# QAn_IP5306_1_0.net
KiCad netlist of a schematic drawn in EAGLE
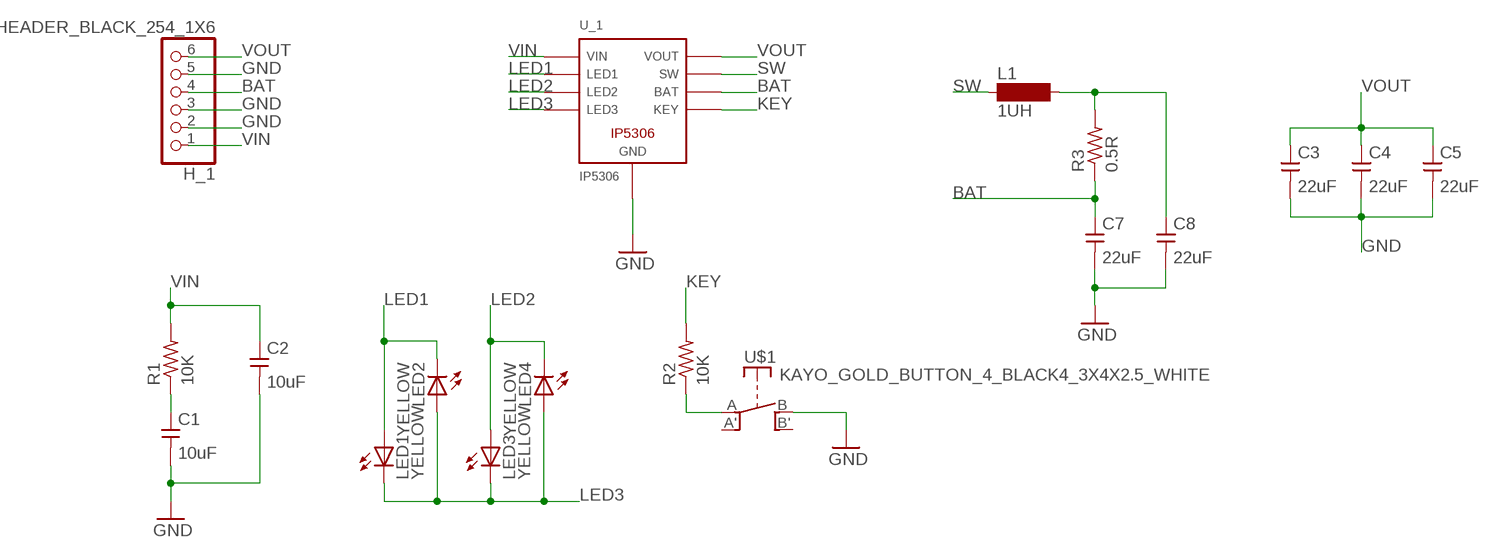
[diagram p0: schematic, sheet 1]

(export (version "E")
  (design (tool "Eeschema 10.0.6"))
  (components
    (comp (ref "C1")
      (value "10uF")
      (footprint "eagle-import:C1206")
      (libsource (lib "eagle-import") (part "KAYO_CAP_CERAMIC_120610UF"))
    )
    (comp (ref "C2")
      (value "10uF")
      (footprint "eagle-import:C1206")
      (libsource (lib "eagle-import") (part "KAYO_CAP_CERAMIC_120610UF"))
    )
    (comp (ref "C3")
      (value "22uF")
      (footprint "eagle-import:C1206")
      (libsource (lib "eagle-import") (part "KAYO_CAP_CERAMIC_120610UF"))
    )
    (comp (ref "C4")
      (value "22uF")
      (footprint "eagle-import:C1206")
      (libsource (lib "eagle-import") (part "KAYO_CAP_CERAMIC_120610UF"))
    )
    (comp (ref "C5")
      (value "22uF")
      (footprint "eagle-import:KXN_C0603")
      (libsource (lib "eagle-import") (part "KAYO_CAP_CERAMIC_KXN_060322UF"))
    )
    (comp (ref "C7")
      (value "22uF")
      (footprint "eagle-import:C1206")
      (libsource (lib "eagle-import") (part "KAYO_CAP_CERAMIC_120610UF"))
    )
    (comp (ref "C8")
      (value "22uF")
      (footprint "eagle-import:C1206")
      (libsource (lib "eagle-import") (part "KAYO_CAP_CERAMIC_120610UF"))
    )
    (comp (ref "H_1")
      (value "HEADER_BLACK_254_1X6")
      (footprint "eagle-import:HEADER_1X6_254_LOCK")
      (libsource (lib "eagle-import") (part "KXN_HEADER_1X6_M_LOCK"))
    )
    (comp (ref "L1")
      (value "1UH")
      (footprint "eagle-import:CKST_0603_0630_PACK")
      (libsource (lib "eagle-import") (part "INDUCTOR_FEEDER_KAYO_0630"))
    )
    (comp (ref "LED1")
      (value "YELLOW")
      (footprint "eagle-import:KXN_LED_0603")
      (libsource (lib "eagle-import") (part "KAYO_LED_KXN_LED_0603_YELLOW"))
    )
    (comp (ref "LED2")
      (value "YELLOW")
      (footprint "eagle-import:KXN_LED_0603")
      (libsource (lib "eagle-import") (part "KAYO_LED_KXN_LED_0603_YELLOW"))
    )
    (comp (ref "LED3")
      (value "YELLOW")
      (footprint "eagle-import:KXN_LED_0603")
      (libsource (lib "eagle-import") (part "KAYO_LED_KXN_LED_0603_YELLOW"))
    )
    (comp (ref "LED4")
      (value "YELLOW")
      (footprint "eagle-import:KXN_LED_0603")
      (libsource (lib "eagle-import") (part "KAYO_LED_KXN_LED_0603_YELLOW"))
    )
    (comp (ref "R1")
      (value "10K")
      (footprint "eagle-import:R0603_KXN")
      (libsource (lib "eagle-import") (part "R-US__R0603_KXN10K"))
    )
    (comp (ref "R2")
      (value "10K")
      (footprint "eagle-import:R0603_KXN")
      (libsource (lib "eagle-import") (part "R-US__R0603_KXN10K"))
    )
    (comp (ref "R3")
      (value "0.5R")
      (footprint "eagle-import:R0603_KXN")
      (libsource (lib "eagle-import") (part "R-US__R0603_KXN"))
    )
    (comp (ref "U$1")
      (value "KAYO_GOLD_BUTTON_4_BLACK4_3X4X2.5_WHITE")
      (footprint "eagle-import:KXN_BUTTON_3_4_2.5MM")
      (libsource (lib "eagle-import") (part "KAYO_GOLD_BUTTON_44_3X4X2.5_WHITE_BLACK"))
    )
    (comp (ref "U_1")
      (value "IP5306")
      (footprint "eagle-import:ESOP8")
      (libsource (lib "eagle-import") (part "IP5306_1"))
    )
  )
  (nets
    (net (code "1") (name "/BAT") (class "Default")
      (node (ref "C7") (pin "1") (pinfunction "+_1") (pintype "passive"))
      (node (ref "H_1") (pin "4") (pinfunction "4_4") (pintype "passive"))
      (node (ref "R3") (pin "1") (pinfunction "1_1") (pintype "passive"))
      (node (ref "U_1") (pin "6") (pinfunction "P$6_6") (pintype "bidirectional"))
    )
    (net (code "2") (name "/KEY") (class "Default")
      (node (ref "R2") (pin "2") (pinfunction "2_2") (pintype "passive"))
      (node (ref "U_1") (pin "5") (pinfunction "P$5_5") (pintype "bidirectional"))
    )
    (net (code "3") (name "/LED1") (class "Default")
      (node (ref "LED1") (pin "A") (pinfunction "A_A") (pintype "passive"))
      (node (ref "LED2") (pin "C") (pinfunction "C_C") (pintype "passive"))
      (node (ref "U_1") (pin "2") (pinfunction "P$2_2") (pintype "bidirectional"))
    )
    (net (code "4") (name "/LED2") (class "Default")
      (node (ref "LED3") (pin "A") (pinfunction "A_A") (pintype "passive"))
      (node (ref "LED4") (pin "C") (pinfunction "C_C") (pintype "passive"))
      (node (ref "U_1") (pin "3") (pinfunction "P$3_3") (pintype "bidirectional"))
    )
    (net (code "5") (name "/LED3") (class "Default")
      (node (ref "LED1") (pin "C") (pinfunction "C_C") (pintype "passive"))
      (node (ref "LED2") (pin "A") (pinfunction "A_A") (pintype "passive"))
      (node (ref "LED3") (pin "C") (pinfunction "C_C") (pintype "passive"))
      (node (ref "LED4") (pin "A") (pinfunction "A_A") (pintype "passive"))
      (node (ref "U_1") (pin "4") (pinfunction "P$4_4") (pintype "bidirectional"))
    )
    (net (code "6") (name "/SW") (class "Default")
      (node (ref "L1") (pin "P$1") (pinfunction "1_P$1") (pintype "passive"))
      (node (ref "U_1") (pin "7") (pinfunction "P$7_7") (pintype "bidirectional"))
    )
    (net (code "7") (name "/VIN") (class "Default")
      (node (ref "C2") (pin "1") (pinfunction "+_1") (pintype "passive"))
      (node (ref "H_1") (pin "1") (pinfunction "1_1") (pintype "passive"))
      (node (ref "R1") (pin "2") (pinfunction "2_2") (pintype "passive"))
      (node (ref "U_1") (pin "1") (pinfunction "P$1_1") (pintype "power_in"))
    )
    (net (code "8") (name "/VOUT") (class "Default")
      (node (ref "C3") (pin "1") (pinfunction "+_1") (pintype "passive"))
      (node (ref "C4") (pin "1") (pinfunction "+_1") (pintype "passive"))
      (node (ref "C5") (pin "1") (pinfunction "+_1") (pintype "passive"))
      (node (ref "H_1") (pin "6") (pinfunction "6_6") (pintype "passive"))
      (node (ref "U_1") (pin "8") (pinfunction "P$8_8") (pintype "power_in"))
    )
    (net (code "9") (name "GND") (class "Default")
      (node (ref "C1") (pin "2") (pinfunction "-_2") (pintype "passive"))
      (node (ref "C2") (pin "2") (pinfunction "-_2") (pintype "passive"))
      (node (ref "C3") (pin "2") (pinfunction "-_2") (pintype "passive"))
      (node (ref "C4") (pin "2") (pinfunction "-_2") (pintype "passive"))
      (node (ref "C5") (pin "2") (pinfunction "-_2") (pintype "passive"))
      (node (ref "C7") (pin "2") (pinfunction "-_2") (pintype "passive"))
      (node (ref "C8") (pin "2") (pinfunction "-_2") (pintype "passive"))
      (node (ref "H_1") (pin "2") (pinfunction "2_2") (pintype "passive"))
      (node (ref "H_1") (pin "3") (pinfunction "3_3") (pintype "passive"))
      (node (ref "H_1") (pin "5") (pinfunction "5_5") (pintype "passive"))
      (node (ref "U$1") (pin "B") (pinfunction "B_B") (pintype "passive"))
      (node (ref "U_1") (pin "9") (pinfunction "P$9_9") (pintype "power_in"))
    )
    (net (code "10") (name "Net-(C1-+)") (class "Default")
      (node (ref "C1") (pin "1") (pinfunction "+_1") (pintype "passive"))
      (node (ref "R1") (pin "1") (pinfunction "1_1") (pintype "passive"))
    )
    (net (code "11") (name "Net-(C8-+)") (class "Default")
      (node (ref "C8") (pin "1") (pinfunction "+_1") (pintype "passive"))
      (node (ref "L1") (pin "P$2") (pinfunction "2_P$2") (pintype "passive"))
      (node (ref "R3") (pin "2") (pinfunction "2_2") (pintype "passive"))
    )
    (net (code "12") (name "Net-(R2-Pad1)") (class "Default")
      (node (ref "R2") (pin "1") (pinfunction "1_1") (pintype "passive"))
      (node (ref "U$1") (pin "A") (pinfunction "A_A") (pintype "passive"))
    )
    (net (code "13") (name "unconnected-(U$1-PadA')") (class "Default")
      (node (ref "U$1") (pin "A'") (pinfunction "A'_A'") (pintype "passive"))
    )
    (net (code "14") (name "unconnected-(U$1-PadB')") (class "Default")
      (node (ref "U$1") (pin "B'") (pinfunction "B'_B'") (pintype "passive"))
    )
  )
)
